# ps2.net
KiCad netlist of a schematic drawn in EAGLE
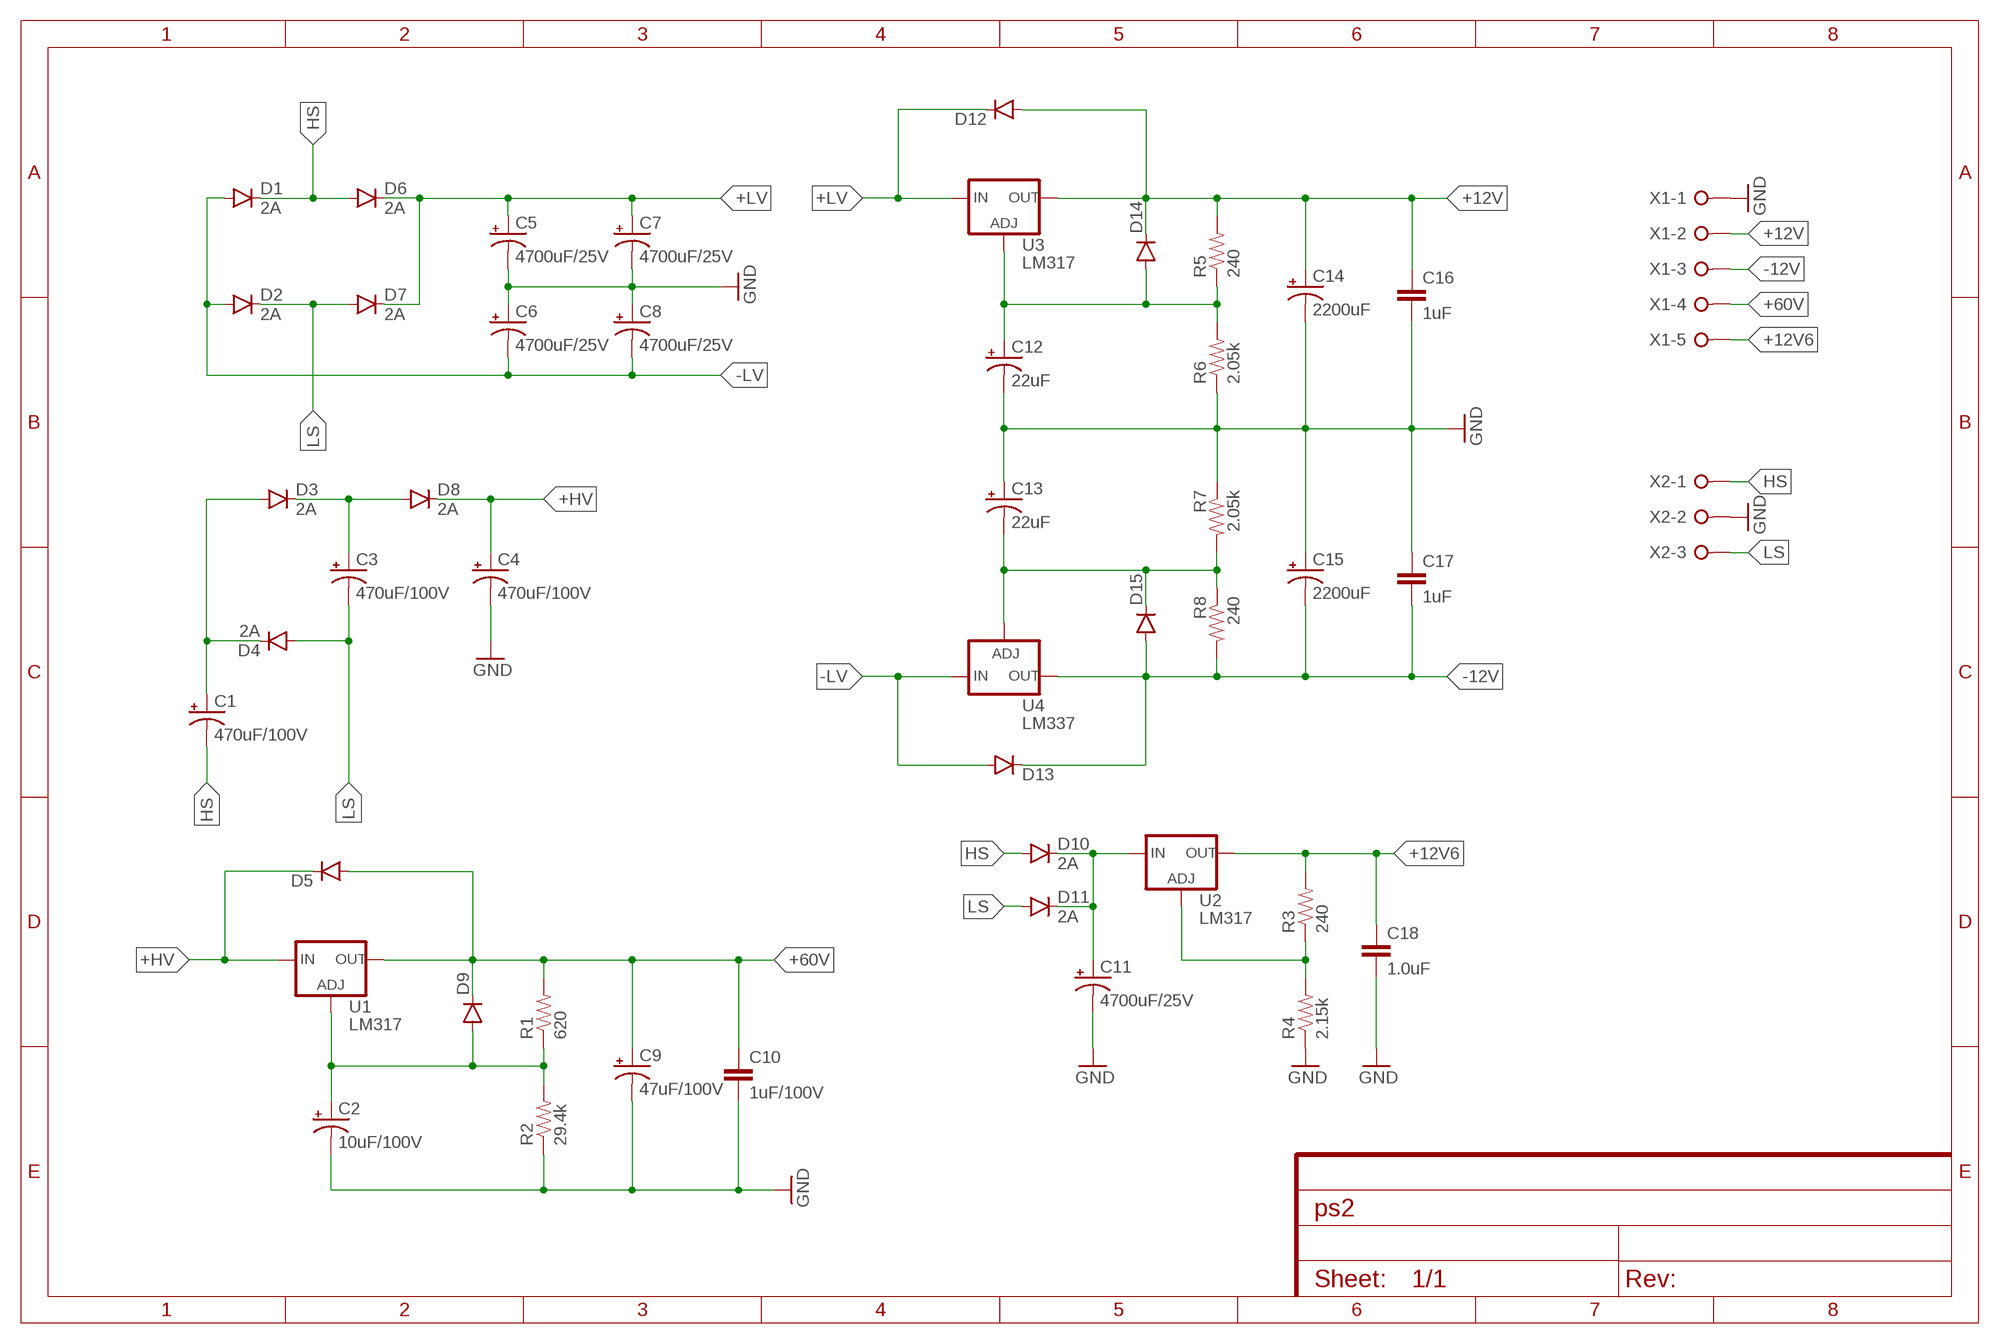
[diagram p0: schematic, sheet 1]

(export (version "E")
  (design (tool "Eeschema 10.0.6"))
  (components
    (comp (ref "C1")
      (value "470uF/100V")
      (footprint "eagle-import:CPOL-RADIAL-1000UF-63V")
      (libsource (lib "eagle-import") (part "CAP_POLPTH3"))
    )
    (comp (ref "C2")
      (value "10uF/100V")
      (footprint "eagle-import:CPOL-RADIAL-100UF-25V")
      (libsource (lib "eagle-import") (part "CAP_POLPTH1"))
    )
    (comp (ref "C3")
      (value "470uF/100V")
      (footprint "eagle-import:CPOL-RADIAL-1000UF-63V")
      (libsource (lib "eagle-import") (part "CAP_POLPTH3"))
    )
    (comp (ref "C4")
      (value "470uF/100V")
      (footprint "eagle-import:CPOL-RADIAL-1000UF-63V")
      (libsource (lib "eagle-import") (part "CAP_POLPTH3"))
    )
    (comp (ref "C5")
      (value "4700uF/25V")
      (footprint "eagle-import:CPOL-RADIAL-1000UF-63V")
      (libsource (lib "eagle-import") (part "CAP_POLPTH3"))
    )
    (comp (ref "C6")
      (value "4700uF/25V")
      (footprint "eagle-import:CPOL-RADIAL-1000UF-63V")
      (libsource (lib "eagle-import") (part "CAP_POLPTH3"))
    )
    (comp (ref "C7")
      (value "4700uF/25V")
      (footprint "eagle-import:CPOL-RADIAL-1000UF-63V")
      (libsource (lib "eagle-import") (part "CAP_POLPTH3"))
    )
    (comp (ref "C8")
      (value "4700uF/25V")
      (footprint "eagle-import:CPOL-RADIAL-1000UF-63V")
      (libsource (lib "eagle-import") (part "CAP_POLPTH3"))
    )
    (comp (ref "C9")
      (value "47uF/100V")
      (footprint "eagle-import:CPOL-RADIAL-1000UF-25V")
      (libsource (lib "eagle-import") (part "CAP_POLPTH4"))
    )
    (comp (ref "C10")
      (value "1uF/100V")
      (footprint "eagle-import:C1206")
      (libsource (lib "eagle-import") (part "C-EUC1206"))
    )
    (comp (ref "C11")
      (value "4700uF/25V")
      (footprint "eagle-import:CPOL-RADIAL-1000UF-63V")
      (libsource (lib "eagle-import") (part "CAP_POLPTH3"))
    )
    (comp (ref "C12")
      (value "22uF")
      (footprint "eagle-import:CPOL-RADIAL-10UF-25V")
      (libsource (lib "eagle-import") (part "CAP_POLPTH2"))
    )
    (comp (ref "C13")
      (value "22uF")
      (footprint "eagle-import:CPOL-RADIAL-10UF-25V")
      (libsource (lib "eagle-import") (part "CAP_POLPTH2"))
    )
    (comp (ref "C14")
      (value "2200uF")
      (footprint "eagle-import:CPOL-RADIAL-1000UF-25V")
      (libsource (lib "eagle-import") (part "CAP_POLPTH4"))
    )
    (comp (ref "C15")
      (value "2200uF")
      (footprint "eagle-import:CPOL-RADIAL-1000UF-25V")
      (libsource (lib "eagle-import") (part "CAP_POLPTH4"))
    )
    (comp (ref "C16")
      (value "1uF")
      (footprint "eagle-import:0805-CAP")
      (libsource (lib "eagle-import") (part "1UF-25V-10%(0805){dblquote}"))
    )
    (comp (ref "C17")
      (value "1uF")
      (footprint "eagle-import:0805-CAP")
      (libsource (lib "eagle-import") (part "1UF-25V-10%(0805){dblquote}"))
    )
    (comp (ref "C18")
      (value "1.0uF")
      (footprint "eagle-import:0805-CAP")
      (libsource (lib "eagle-import") (part "1.0UF-25V-+80/-20(0805){dblquote}"))
    )
    (comp (ref "D1")
      (value "2A")
      (footprint "eagle-import:SMA-DIODE")
      (libsource (lib "eagle-import") (part "DIODESMA"))
    )
    (comp (ref "D2")
      (value "2A")
      (footprint "eagle-import:SMA-DIODE")
      (libsource (lib "eagle-import") (part "DIODESMA"))
    )
    (comp (ref "D3")
      (value "2A")
      (footprint "eagle-import:SMA-DIODE")
      (libsource (lib "eagle-import") (part "DIODESMA"))
    )
    (comp (ref "D4")
      (value "2A")
      (footprint "eagle-import:SMA-DIODE")
      (libsource (lib "eagle-import") (part "DIODESMA"))
    )
    (comp (ref "D5")
      (value "DIODESMA")
      (footprint "eagle-import:SMA-DIODE")
      (libsource (lib "eagle-import") (part "DIODESMA"))
    )
    (comp (ref "D6")
      (value "2A")
      (footprint "eagle-import:SMA-DIODE")
      (libsource (lib "eagle-import") (part "DIODESMA"))
    )
    (comp (ref "D7")
      (value "2A")
      (footprint "eagle-import:SMA-DIODE")
      (libsource (lib "eagle-import") (part "DIODESMA"))
    )
    (comp (ref "D8")
      (value "2A")
      (footprint "eagle-import:SMA-DIODE")
      (libsource (lib "eagle-import") (part "DIODESMA"))
    )
    (comp (ref "D9")
      (value "DIODESMA")
      (footprint "eagle-import:SMA-DIODE")
      (libsource (lib "eagle-import") (part "DIODESMA"))
    )
    (comp (ref "D10")
      (value "2A")
      (footprint "eagle-import:SMA-DIODE")
      (libsource (lib "eagle-import") (part "DIODESMA"))
    )
    (comp (ref "D11")
      (value "2A")
      (footprint "eagle-import:SMA-DIODE")
      (libsource (lib "eagle-import") (part "DIODESMA"))
    )
    (comp (ref "D12")
      (value "DIODESMA")
      (footprint "eagle-import:SMA-DIODE")
      (libsource (lib "eagle-import") (part "DIODESMA"))
    )
    (comp (ref "D13")
      (value "DIODESMA")
      (footprint "eagle-import:SMA-DIODE")
      (libsource (lib "eagle-import") (part "DIODESMA"))
    )
    (comp (ref "D14")
      (value "DIODESMA")
      (footprint "eagle-import:SMA-DIODE")
      (libsource (lib "eagle-import") (part "DIODESMA"))
    )
    (comp (ref "D15")
      (value "DIODESMA")
      (footprint "eagle-import:SMA-DIODE")
      (libsource (lib "eagle-import") (part "DIODESMA"))
    )
    (comp (ref "R1")
      (value "620")
      (footprint "eagle-import:AXIAL-0.4")
      (libsource (lib "eagle-import") (part "RESISTORPTH-1/4W"))
    )
    (comp (ref "R2")
      (value "29.4k")
      (footprint "eagle-import:AXIAL-0.4")
      (libsource (lib "eagle-import") (part "RESISTORPTH-1/4W"))
    )
    (comp (ref "R3")
      (value "240")
      (footprint "eagle-import:AXIAL-0.4")
      (libsource (lib "eagle-import") (part "RESISTORPTH-1/4W"))
    )
    (comp (ref "R4")
      (value "2.15k")
      (footprint "eagle-import:AXIAL-0.4")
      (libsource (lib "eagle-import") (part "RESISTORPTH-1/4W"))
    )
    (comp (ref "R5")
      (value "240")
      (footprint "eagle-import:AXIAL-0.4")
      (libsource (lib "eagle-import") (part "RESISTORPTH-1/4W"))
    )
    (comp (ref "R6")
      (value "2.05k")
      (footprint "eagle-import:AXIAL-0.4")
      (libsource (lib "eagle-import") (part "RESISTORPTH-1/4W"))
    )
    (comp (ref "R7")
      (value "2.05k")
      (footprint "eagle-import:AXIAL-0.4")
      (libsource (lib "eagle-import") (part "RESISTORPTH-1/4W"))
    )
    (comp (ref "R8")
      (value "240")
      (footprint "eagle-import:AXIAL-0.4")
      (libsource (lib "eagle-import") (part "RESISTORPTH-1/4W"))
    )
    (comp (ref "U1")
      (value "LM317")
      (footprint "eagle-import:V-REG_DPACK")
      (libsource (lib "eagle-import") (part "V_REG_317DPACK"))
    )
    (comp (ref "U2")
      (value "LM317")
      (footprint "eagle-import:V-REG_DPACK")
      (libsource (lib "eagle-import") (part "V_REG_317DPACK"))
    )
    (comp (ref "U3")
      (value "LM317")
      (footprint "eagle-import:V-REG_DPACK")
      (libsource (lib "eagle-import") (part "V_REG_317DPACK"))
    )
    (comp (ref "U4")
      (value "LM337")
      (footprint "eagle-import:V-REG_DPACK")
      (libsource (lib "eagle-import") (part "V_REG_337DPACK"))
    )
    (comp (ref "X1")
      (value "W237-05P")
      (footprint "eagle-import:W237-5P")
      (libsource (lib "eagle-import") (part "W237-05P"))
    )
    (comp (ref "X2")
      (value "W237-3E")
      (footprint "eagle-import:W237-3E")
      (libsource (lib "eagle-import") (part "W237-3E"))
    )
  )
  (nets
    (net (code "1") (name "+12V") (class "Default")
      (node (ref "C14") (pin "+") (pinfunction "+_+") (pintype "passive"))
      (node (ref "C16") (pin "1") (pinfunction "1_1") (pintype "passive"))
      (node (ref "D12") (pin "A") (pinfunction "A_A") (pintype "passive"))
      (node (ref "D14") (pin "C") (pinfunction "C_C") (pintype "passive"))
      (node (ref "R5") (pin "P$2") (pinfunction "2_P$2") (pintype "passive"))
      (node (ref "U3") (pin "4") (pinfunction "OUT_4") (pintype "output"))
      (node (ref "X1") (pin "2") (pinfunction "KL_2") (pintype "passive"))
    )
    (net (code "2") (name "+12V6") (class "Default")
      (node (ref "C18") (pin "1") (pinfunction "1_1") (pintype "passive"))
      (node (ref "R3") (pin "P$2") (pinfunction "2_P$2") (pintype "passive"))
      (node (ref "U2") (pin "4") (pinfunction "OUT_4") (pintype "output"))
      (node (ref "X1") (pin "5") (pinfunction "KL_5") (pintype "passive"))
    )
    (net (code "3") (name "+60V") (class "Default")
      (node (ref "C10") (pin "1") (pinfunction "1_1") (pintype "passive"))
      (node (ref "C9") (pin "+") (pinfunction "+_+") (pintype "passive"))
      (node (ref "D5") (pin "A") (pinfunction "A_A") (pintype "passive"))
      (node (ref "D9") (pin "C") (pinfunction "C_C") (pintype "passive"))
      (node (ref "R1") (pin "P$2") (pinfunction "2_P$2") (pintype "passive"))
      (node (ref "U1") (pin "4") (pinfunction "OUT_4") (pintype "output"))
      (node (ref "X1") (pin "4") (pinfunction "KL_4") (pintype "passive"))
    )
    (net (code "4") (name "+HV") (class "Default")
      (node (ref "C4") (pin "1") (pinfunction "+_1") (pintype "passive"))
      (node (ref "D5") (pin "C") (pinfunction "C_C") (pintype "passive"))
      (node (ref "D8") (pin "C") (pinfunction "C_C") (pintype "passive"))
      (node (ref "U1") (pin "3") (pinfunction "IN_3") (pintype "input"))
    )
    (net (code "5") (name "+LV") (class "Default")
      (node (ref "C5") (pin "1") (pinfunction "+_1") (pintype "passive"))
      (node (ref "C7") (pin "1") (pinfunction "+_1") (pintype "passive"))
      (node (ref "D12") (pin "C") (pinfunction "C_C") (pintype "passive"))
      (node (ref "D6") (pin "C") (pinfunction "C_C") (pintype "passive"))
      (node (ref "D7") (pin "C") (pinfunction "C_C") (pintype "passive"))
      (node (ref "U3") (pin "3") (pinfunction "IN_3") (pintype "input"))
    )
    (net (code "6") (name "-12V") (class "Default")
      (node (ref "C15") (pin "-") (pinfunction "-_-") (pintype "passive"))
      (node (ref "C17") (pin "2") (pinfunction "2_2") (pintype "passive"))
      (node (ref "D13") (pin "C") (pinfunction "C_C") (pintype "passive"))
      (node (ref "D15") (pin "A") (pinfunction "A_A") (pintype "passive"))
      (node (ref "R8") (pin "P$2") (pinfunction "2_P$2") (pintype "passive"))
      (node (ref "U4") (pin "3") (pinfunction "OUT_3") (pintype "output"))
      (node (ref "X1") (pin "3") (pinfunction "KL_3") (pintype "passive"))
    )
    (net (code "7") (name "-LV") (class "Default")
      (node (ref "C6") (pin "2") (pinfunction "-_2") (pintype "passive"))
      (node (ref "C8") (pin "2") (pinfunction "-_2") (pintype "passive"))
      (node (ref "D1") (pin "A") (pinfunction "A_A") (pintype "passive"))
      (node (ref "D13") (pin "A") (pinfunction "A_A") (pintype "passive"))
      (node (ref "D2") (pin "A") (pinfunction "A_A") (pintype "passive"))
      (node (ref "U4") (pin "2") (pinfunction "IN_2") (pintype "input"))
    )
    (net (code "8") (name "GND") (class "Default")
      (node (ref "C10") (pin "2") (pinfunction "2_2") (pintype "passive"))
      (node (ref "C11") (pin "2") (pinfunction "-_2") (pintype "passive"))
      (node (ref "C12") (pin "2") (pinfunction "-_2") (pintype "passive"))
      (node (ref "C13") (pin "1") (pinfunction "+_1") (pintype "passive"))
      (node (ref "C14") (pin "-") (pinfunction "-_-") (pintype "passive"))
      (node (ref "C15") (pin "+") (pinfunction "+_+") (pintype "passive"))
      (node (ref "C16") (pin "2") (pinfunction "2_2") (pintype "passive"))
      (node (ref "C17") (pin "1") (pinfunction "1_1") (pintype "passive"))
      (node (ref "C18") (pin "2") (pinfunction "2_2") (pintype "passive"))
      (node (ref "C2") (pin "2") (pinfunction "-_2") (pintype "passive"))
      (node (ref "C4") (pin "2") (pinfunction "-_2") (pintype "passive"))
      (node (ref "C5") (pin "2") (pinfunction "-_2") (pintype "passive"))
      (node (ref "C6") (pin "1") (pinfunction "+_1") (pintype "passive"))
      (node (ref "C7") (pin "2") (pinfunction "-_2") (pintype "passive"))
      (node (ref "C8") (pin "1") (pinfunction "+_1") (pintype "passive"))
      (node (ref "C9") (pin "-") (pinfunction "-_-") (pintype "passive"))
      (node (ref "R2") (pin "P$1") (pinfunction "1_P$1") (pintype "passive"))
      (node (ref "R4") (pin "P$1") (pinfunction "1_P$1") (pintype "passive"))
      (node (ref "R6") (pin "P$1") (pinfunction "1_P$1") (pintype "passive"))
      (node (ref "R7") (pin "P$1") (pinfunction "1_P$1") (pintype "passive"))
      (node (ref "X1") (pin "1") (pinfunction "KL_1") (pintype "passive"))
      (node (ref "X2") (pin "2") (pinfunction "KL_2") (pintype "passive"))
    )
    (net (code "9") (name "HS") (class "Default")
      (node (ref "C1") (pin "2") (pinfunction "-_2") (pintype "passive"))
      (node (ref "D1") (pin "C") (pinfunction "C_C") (pintype "passive"))
      (node (ref "D10") (pin "A") (pinfunction "A_A") (pintype "passive"))
      (node (ref "D6") (pin "A") (pinfunction "A_A") (pintype "passive"))
      (node (ref "X2") (pin "1") (pinfunction "KL_1") (pintype "passive"))
    )
    (net (code "10") (name "LS") (class "Default")
      (node (ref "C3") (pin "2") (pinfunction "-_2") (pintype "passive"))
      (node (ref "D11") (pin "A") (pinfunction "A_A") (pintype "passive"))
      (node (ref "D2") (pin "C") (pinfunction "C_C") (pintype "passive"))
      (node (ref "D4") (pin "A") (pinfunction "A_A") (pintype "passive"))
      (node (ref "D7") (pin "A") (pinfunction "A_A") (pintype "passive"))
      (node (ref "X2") (pin "3") (pinfunction "KL_3") (pintype "passive"))
    )
    (net (code "11") (name "Net-(C1-+)") (class "Default")
      (node (ref "C1") (pin "1") (pinfunction "+_1") (pintype "passive"))
      (node (ref "D3") (pin "A") (pinfunction "A_A") (pintype "passive"))
      (node (ref "D4") (pin "C") (pinfunction "C_C") (pintype "passive"))
    )
    (net (code "12") (name "Net-(C2-+)") (class "Default")
      (node (ref "C2") (pin "1") (pinfunction "+_1") (pintype "passive"))
      (node (ref "D9") (pin "A") (pinfunction "A_A") (pintype "passive"))
      (node (ref "R1") (pin "P$1") (pinfunction "1_P$1") (pintype "passive"))
      (node (ref "R2") (pin "P$2") (pinfunction "2_P$2") (pintype "passive"))
      (node (ref "U1") (pin "1") (pinfunction "ADJ_1") (pintype "input"))
    )
    (net (code "13") (name "Net-(C3-+)") (class "Default")
      (node (ref "C3") (pin "1") (pinfunction "+_1") (pintype "passive"))
      (node (ref "D3") (pin "C") (pinfunction "C_C") (pintype "passive"))
      (node (ref "D8") (pin "A") (pinfunction "A_A") (pintype "passive"))
    )
    (net (code "14") (name "Net-(C11-+)") (class "Default")
      (node (ref "C11") (pin "1") (pinfunction "+_1") (pintype "passive"))
      (node (ref "D10") (pin "C") (pinfunction "C_C") (pintype "passive"))
      (node (ref "D11") (pin "C") (pinfunction "C_C") (pintype "passive"))
      (node (ref "U2") (pin "3") (pinfunction "IN_3") (pintype "input"))
    )
    (net (code "15") (name "Net-(C12-+)") (class "Default")
      (node (ref "C12") (pin "1") (pinfunction "+_1") (pintype "passive"))
      (node (ref "D14") (pin "A") (pinfunction "A_A") (pintype "passive"))
      (node (ref "R5") (pin "P$1") (pinfunction "1_P$1") (pintype "passive"))
      (node (ref "R6") (pin "P$2") (pinfunction "2_P$2") (pintype "passive"))
      (node (ref "U3") (pin "1") (pinfunction "ADJ_1") (pintype "input"))
    )
    (net (code "16") (name "Net-(C13--)") (class "Default")
      (node (ref "C13") (pin "2") (pinfunction "-_2") (pintype "passive"))
      (node (ref "D15") (pin "C") (pinfunction "C_C") (pintype "passive"))
      (node (ref "R7") (pin "P$2") (pinfunction "2_P$2") (pintype "passive"))
      (node (ref "R8") (pin "P$1") (pinfunction "1_P$1") (pintype "passive"))
      (node (ref "U4") (pin "1") (pinfunction "ADJ_1") (pintype "input"))
    )
    (net (code "17") (name "Net-(R3-1)") (class "Default")
      (node (ref "R3") (pin "P$1") (pinfunction "1_P$1") (pintype "passive"))
      (node (ref "R4") (pin "P$2") (pinfunction "2_P$2") (pintype "passive"))
      (node (ref "U2") (pin "1") (pinfunction "ADJ_1") (pintype "input"))
    )
  )
)
